# Power.net
KiCad netlist of a schematic drawn in Altium Designer
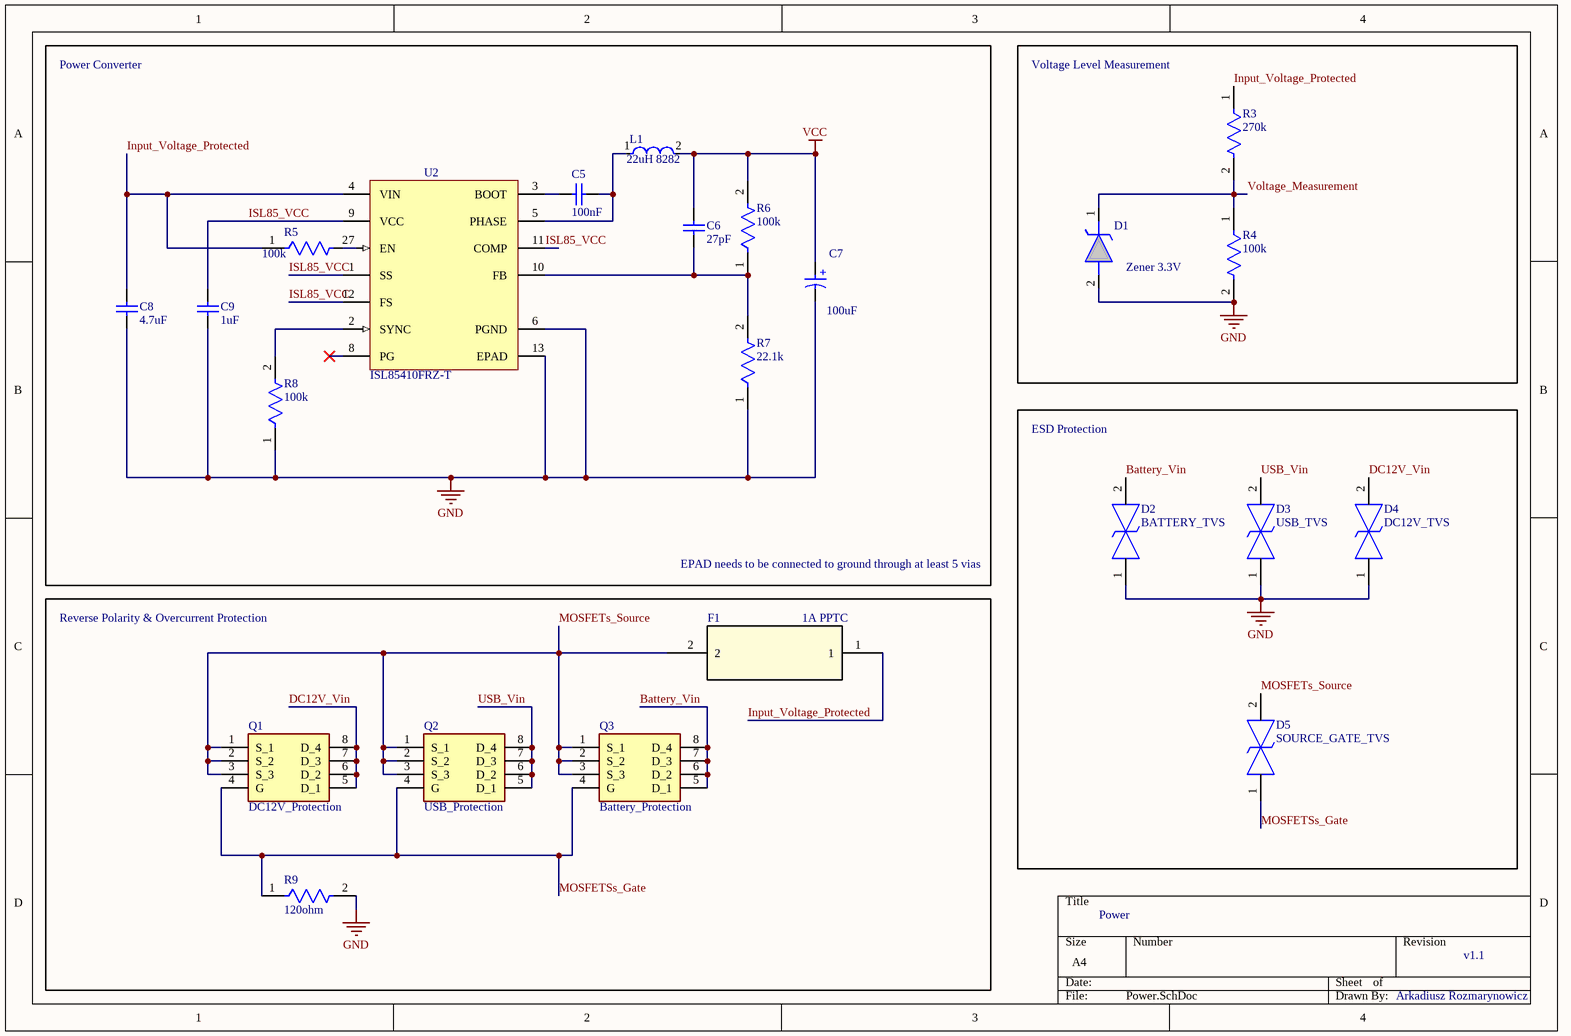
[diagram p0: Power.SchDoc]

(export (version "E")
  (design (tool "Eeschema 10.0.6"))
  (components
    (comp (ref "C5")
      (value "100nF")
      (footprint "CAPC2013X145X48NL20T23")
      (fields (field (name "PART NUMBER") "VJ0805Y104KXAMR") (field (name "MANUFACTURER") "Vitramon"))
      (libsource (lib "Altium Content Vault") (part "CAP"))
    )
    (comp (ref "C6")
      (value "27pF")
      (footprint "CAPC2013X145X48NL20T23")
      (fields (field (name "PART NUMBER") "VJ0805Y104KXAMR") (field (name "MANUFACTURER") "Vitramon"))
      (libsource (lib "Altium Content Vault") (part "CAP"))
    )
    (comp (ref "C7")
      (value "100uF")
      (footprint "WCAP-ASLI_D6.3H7.7")
      (description "Cap Aluminum Lytic 100uF 35V 20% (6.3 X 7.7mm) SMD 300mA 2000h 105C T/R")
      (fields (field (name "TOLERANCE") "20%"))
      (libsource (lib "Altium Content Vault") (part "Capacitor_Polarized"))
    )
    (comp (ref "C8")
      (value "4.7uF")
      (footprint "CAPC2013X145X48NL20T23")
      (fields (field (name "PART NUMBER") "VJ0805Y104KXAMR") (field (name "MANUFACTURER") "Vitramon"))
      (libsource (lib "Altium Content Vault") (part "CAP"))
    )
    (comp (ref "C9")
      (value "1uF")
      (footprint "CAPC2013X145X48NL20T23")
      (fields (field (name "PART NUMBER") "VJ0805Y104KXAMR") (field (name "MANUFACTURER") "Vitramon"))
      (libsource (lib "Altium Content Vault") (part "CAP"))
    )
    (comp (ref "D1")
      (value "Zener 3.3V")
      (footprint "ZMM33B")
      (description "SMD Planra Zener Diode")
      (fields
        (field (name "MANUFACTURER_PART_NUMBER") "ZMM33B")
        (field (name "MOUSER PART NUMBER") "637-ZMM33B")
      )
      (libsource (lib "ZMM33B") (part "ZMM33B"))
    )
    (comp (ref "D2")
      (value "BATTERY_TVS")
      (footprint "DIONM5127X250N")
      (description "19.9V Clamp 30.2A Ipp Tvs Diode Surface Mount DO-214AC (SMA)")
      (fields (field (name "MANUFACTURER_PART_NUMBER") "SMAJ12CA-HP6AT/13"))
      (libsource (lib "SMAJ12CA-HP6AT_13") (part "SMAJ12CA-HP6AT_13"))
    )
    (comp (ref "D3")
      (value "USB_TVS")
      (footprint "DIONM5127X250N")
      (description "19.9V Clamp 30.2A Ipp Tvs Diode Surface Mount DO-214AC (SMA)")
      (fields (field (name "MANUFACTURER_PART_NUMBER") "SMAJ12CA-HP6AT/13"))
      (libsource (lib "SMAJ12CA-HP6AT_13") (part "SMAJ12CA-HP6AT_13"))
    )
    (comp (ref "D4")
      (value "DC12V_TVS")
      (footprint "DIONM5127X250N")
      (description "19.9V Clamp 30.2A Ipp Tvs Diode Surface Mount DO-214AC (SMA)")
      (fields (field (name "MANUFACTURER_PART_NUMBER") "SMAJ12CA-HP6AT/13"))
      (libsource (lib "SMAJ12CA-HP6AT_13") (part "SMAJ12CA-HP6AT_13"))
    )
    (comp (ref "D5")
      (value "SOURCE_GATE_TVS")
      (footprint "DIONM5127X250N")
      (description "19.9V Clamp 30.2A Ipp Tvs Diode Surface Mount DO-214AC (SMA)")
      (fields (field (name "MANUFACTURER_PART_NUMBER") "SMAJ12CA-HP6AT/13"))
      (libsource (lib "SMAJ12CA-HP6AT_13") (part "SMAJ12CA-HP6AT_13"))
    )
    (comp (ref "F1")
      (value "1A PPTC")
      (footprint "CHIP_ 0603L_1P8X1_LTF")
      (description "PPTC")
      (fields
        (field (name "MANUFACTURER_PART_NUMBER") "0603L100SLYR")
        (field (name "COPYRIGHT") "Copyright (C) 2025 Ultra Librarian. All rights reserved.")
      )
      (libsource (lib "0603L100SLYR") (part "0603L100SLYR"))
    )
    (comp (ref "L1")
      (value "22uH 8282")
      (footprint "FP-IHLP-3232DZ-FP_2_413x5-MFG")
      (description "Commercial Inductors, High Temperature (155 °C) Series 22uH 3.7A 110.21mΩ 20%")
      (fields (field (name "TOLERANCE") "20%"))
      (libsource (lib "Altium Content Vault") (part "725321dda6339637d4d059423bc1c3c"))
    )
    (comp (ref "Q1")
      (value "DC12V_Protection")
      (footprint "SOIC127P600X170-8N")
      (description "MOSFET P Channel 30V 7.1A 2.1V @ 250uA 45m @ 6A,10V SOP-8_150mil RoHS")
      (fields
        (field (name "MANUFACTURER_PART_NUMBER") "DMP3056LSS-13")
        (field (name "MOUSER PART NUMBER") "621-DMP3056LSS-13")
      )
      (libsource (lib "DMP3056LSS-13") (part "DMP3056LSS-13"))
    )
    (comp (ref "Q2")
      (value "USB_Protection")
      (footprint "SOIC127P600X170-8N")
      (description "MOSFET P Channel 30V 7.1A 2.1V @ 250uA 45m @ 6A,10V SOP-8_150mil RoHS")
      (fields
        (field (name "MANUFACTURER_PART_NUMBER") "DMP3056LSS-13")
        (field (name "MOUSER PART NUMBER") "621-DMP3056LSS-13")
      )
      (libsource (lib "DMP3056LSS-13") (part "DMP3056LSS-13"))
    )
    (comp (ref "Q3")
      (value "Battery_Protection")
      (footprint "SOIC127P600X170-8N")
      (description "MOSFET P Channel 30V 7.1A 2.1V @ 250uA 45m @ 6A,10V SOP-8_150mil RoHS")
      (fields
        (field (name "MANUFACTURER_PART_NUMBER") "DMP3056LSS-13")
        (field (name "MOUSER PART NUMBER") "621-DMP3056LSS-13")
      )
      (libsource (lib "DMP3056LSS-13") (part "DMP3056LSS-13"))
    )
    (comp (ref "R3")
      (value "270k")
      (footprint "FP-CRGCQ0805-IPC_C")
      (description "CRGCQ0805 10KΩ 0.125W ±100ppm/°C 5% 150V")
      (fields
        (field (name "TOLERANCE") "0.05")
        (field (name "OCTOPART") "https://octopart.com/crgcq0805j100k-te+connectivity-91018199")
      )
      (libsource (lib "Altium Content Vault") (part "1029c3af85768c4190bb7ad29bc67b5"))
    )
    (comp (ref "R4")
      (value "100k")
      (footprint "FP-CRGCQ0805-IPC_C")
      (description "CRGCQ0805 10KΩ 0.125W ±100ppm/°C 5% 150V")
      (fields
        (field (name "TOLERANCE") "0.05")
        (field (name "OCTOPART") "https://octopart.com/crgcq0805j100k-te+connectivity-91018199")
      )
      (libsource (lib "Altium Content Vault") (part "1029c3af85768c4190bb7ad29bc67b5"))
    )
    (comp (ref "R5")
      (value "100k")
      (footprint "FP-CRGCQ0805-IPC_C")
      (description "CRGCQ0805 100KΩ 0.125W ±100ppm/°C 5% 150V")
      (fields
        (field (name "TOLERANCE") "0.05")
        (field (name "OCTOPART") "https://octopart.com/crgcq0805j100k-te+connectivity-91018199")
      )
      (libsource (lib "Altium Content Vault") (part "1029c3af85768c4190bb7ad29bc67b5"))
    )
    (comp (ref "R6")
      (value "100k")
      (footprint "FP-CRGCQ0805-IPC_C")
      (description "CRGCQ0805 100KΩ 0.125W ±100ppm/°C 5% 150V")
      (fields
        (field (name "TOLERANCE") "0.05")
        (field (name "OCTOPART") "https://octopart.com/crgcq0805j100k-te+connectivity-91018199")
      )
      (libsource (lib "Altium Content Vault") (part "1029c3af85768c4190bb7ad29bc67b5"))
    )
    (comp (ref "R7")
      (value "22.1k")
      (footprint "FP-CRGCQ0805-IPC_C")
      (description "CRGCQ0805 100KΩ 0.125W ±100ppm/°C 5% 150V")
      (fields
        (field (name "TOLERANCE") "0.05")
        (field (name "OCTOPART") "https://octopart.com/crgcq0805j100k-te+connectivity-91018199")
      )
      (libsource (lib "Altium Content Vault") (part "1029c3af85768c4190bb7ad29bc67b5"))
    )
    (comp (ref "R8")
      (value "100k")
      (footprint "FP-CRGCQ0805-IPC_C")
      (description "CRGCQ0805 100KΩ 0.125W ±100ppm/°C 5% 150V")
      (fields
        (field (name "TOLERANCE") "0.05")
        (field (name "OCTOPART") "https://octopart.com/crgcq0805j100k-te+connectivity-91018199")
      )
      (libsource (lib "Altium Content Vault") (part "1029c3af85768c4190bb7ad29bc67b5"))
    )
    (comp (ref "R9")
      (value "120ohm")
      (footprint "FP-CRGCQ0805-IPC_C")
      (description "CRGCQ0805 10KΩ 0.125W ±100ppm/°C 5% 150V")
      (fields
        (field (name "TOLERANCE") "0.05")
        (field (name "OCTOPART") "https://octopart.com/crgcq0805j100k-te+connectivity-91018199")
      )
      (libsource (lib "Altium Content Vault") (part "1029c3af85768c4190bb7ad29bc67b5"))
    )
    (comp (ref "U2")
      (value "ISL85410FRZ-T")
      (footprint "L12_4x3_MFG")
      (description "Inverter RoHS Compliant Adjustable Positive Switching Regulator IC 125C 2MHz 1A 82.298666mg")
      (libsource (lib "Altium Content Vault") (part "27339be89be241b5cf71551e81944d9"))
    )
  )
  (nets
    (net (code "1") (name "/Battery_Vin") (class "Default")
      (node (ref "D2") (pin "2") (pinfunction "2_2") (pintype "passive"))
      (node (ref "Q3") (pin "5") (pinfunction "D_1_5") (pintype "passive"))
      (node (ref "Q3") (pin "6") (pinfunction "D_2_6") (pintype "passive"))
      (node (ref "Q3") (pin "7") (pinfunction "D_3_7") (pintype "passive"))
      (node (ref "Q3") (pin "8") (pinfunction "D_4_8") (pintype "passive"))
    )
    (net (code "2") (name "/DC12V_Vin") (class "Default")
      (node (ref "D4") (pin "2") (pinfunction "2_2") (pintype "passive"))
      (node (ref "Q1") (pin "5") (pinfunction "D_1_5") (pintype "passive"))
      (node (ref "Q1") (pin "6") (pinfunction "D_2_6") (pintype "passive"))
      (node (ref "Q1") (pin "7") (pinfunction "D_3_7") (pintype "passive"))
      (node (ref "Q1") (pin "8") (pinfunction "D_4_8") (pintype "passive"))
    )
    (net (code "3") (name "/ISL85_VCC") (class "Default")
      (node (ref "C9") (pin "2") (pinfunction "2_2") (pintype "passive"))
      (node (ref "U2") (pin "1") (pinfunction "SS_1") (pintype "passive"))
      (node (ref "U2") (pin "11") (pinfunction "COMP_11") (pintype "passive"))
      (node (ref "U2") (pin "12") (pinfunction "FS_12") (pintype "passive"))
      (node (ref "U2") (pin "9") (pinfunction "VCC_9") (pintype "power_in"))
    )
    (net (code "4") (name "/Input_Voltage_Protected") (class "Default")
      (node (ref "C8") (pin "2") (pinfunction "2_2") (pintype "passive"))
      (node (ref "F1") (pin "1") (pinfunction "1_1") (pintype "passive"))
      (node (ref "R3") (pin "1") (pinfunction "1_1") (pintype "passive"))
      (node (ref "R5") (pin "1") (pinfunction "1_1") (pintype "passive"))
      (node (ref "U2") (pin "4") (pinfunction "VIN_4") (pintype "power_in"))
    )
    (net (code "5") (name "/MOSFETSs_Gate") (class "Default")
      (node (ref "D5") (pin "1") (pinfunction "1_1") (pintype "passive"))
      (node (ref "Q1") (pin "4") (pinfunction "G_4") (pintype "passive"))
      (node (ref "Q2") (pin "4") (pinfunction "G_4") (pintype "passive"))
      (node (ref "Q3") (pin "4") (pinfunction "G_4") (pintype "passive"))
      (node (ref "R9") (pin "1") (pinfunction "1_1") (pintype "passive"))
    )
    (net (code "6") (name "/MOSFETs_Source") (class "Default")
      (node (ref "D5") (pin "2") (pinfunction "2_2") (pintype "passive"))
      (node (ref "F1") (pin "2") (pinfunction "2_2") (pintype "passive"))
      (node (ref "Q1") (pin "1") (pinfunction "S_1_1") (pintype "passive"))
      (node (ref "Q1") (pin "2") (pinfunction "S_2_2") (pintype "passive"))
      (node (ref "Q1") (pin "3") (pinfunction "S_3_3") (pintype "passive"))
      (node (ref "Q2") (pin "1") (pinfunction "S_1_1") (pintype "passive"))
      (node (ref "Q2") (pin "2") (pinfunction "S_2_2") (pintype "passive"))
      (node (ref "Q2") (pin "3") (pinfunction "S_3_3") (pintype "passive"))
      (node (ref "Q3") (pin "1") (pinfunction "S_1_1") (pintype "passive"))
      (node (ref "Q3") (pin "2") (pinfunction "S_2_2") (pintype "passive"))
      (node (ref "Q3") (pin "3") (pinfunction "S_3_3") (pintype "passive"))
    )
    (net (code "7") (name "/USB_Vin") (class "Default")
      (node (ref "D3") (pin "2") (pinfunction "2_2") (pintype "passive"))
      (node (ref "Q2") (pin "5") (pinfunction "D_1_5") (pintype "passive"))
      (node (ref "Q2") (pin "6") (pinfunction "D_2_6") (pintype "passive"))
      (node (ref "Q2") (pin "7") (pinfunction "D_3_7") (pintype "passive"))
      (node (ref "Q2") (pin "8") (pinfunction "D_4_8") (pintype "passive"))
    )
    (net (code "8") (name "/Voltage_Measurement") (class "Default")
      (node (ref "D1") (pin "1") (pinfunction "K_1") (pintype "passive"))
      (node (ref "R3") (pin "2") (pinfunction "2_2") (pintype "passive"))
      (node (ref "R4") (pin "1") (pinfunction "1_1") (pintype "passive"))
    )
    (net (code "9") (name "GND") (class "Default")
      (node (ref "C7") (pin "2") (pinfunction "N_2") (pintype "passive"))
      (node (ref "C8") (pin "1") (pinfunction "1_1") (pintype "passive"))
      (node (ref "C9") (pin "1") (pinfunction "1_1") (pintype "passive"))
      (node (ref "D1") (pin "2") (pinfunction "A_2") (pintype "passive"))
      (node (ref "D2") (pin "1") (pinfunction "1_1") (pintype "passive"))
      (node (ref "D3") (pin "1") (pinfunction "1_1") (pintype "passive"))
      (node (ref "D4") (pin "1") (pinfunction "1_1") (pintype "passive"))
      (node (ref "R4") (pin "2") (pinfunction "2_2") (pintype "passive"))
      (node (ref "R7") (pin "1") (pinfunction "1_1") (pintype "passive"))
      (node (ref "R8") (pin "1") (pinfunction "1_1") (pintype "passive"))
      (node (ref "R9") (pin "2") (pinfunction "2_2") (pintype "passive"))
      (node (ref "U2") (pin "13") (pinfunction "EPAD_13") (pintype "power_in"))
      (node (ref "U2") (pin "6") (pinfunction "PGND_6") (pintype "power_in"))
    )
    (net (code "10") (name "Net-(U2-BOOT)") (class "Default")
      (node (ref "C5") (pin "2") (pinfunction "2_2") (pintype "passive"))
      (node (ref "U2") (pin "3") (pinfunction "BOOT_3") (pintype "passive"))
    )
    (net (code "11") (name "Net-(U2-EN)") (class "Default")
      (node (ref "R5") (pin "2") (pinfunction "2_2") (pintype "passive"))
      (node (ref "U2") (pin "7") (pinfunction "EN_7") (pintype "input"))
    )
    (net (code "12") (name "Net-(U2-FB)") (class "Default")
      (node (ref "C6") (pin "1") (pinfunction "1_1") (pintype "passive"))
      (node (ref "R6") (pin "1") (pinfunction "1_1") (pintype "passive"))
      (node (ref "R7") (pin "2") (pinfunction "2_2") (pintype "passive"))
      (node (ref "U2") (pin "10") (pinfunction "FB_10") (pintype "passive"))
    )
    (net (code "13") (name "Net-(U2-PHASE)") (class "Default")
      (node (ref "C5") (pin "1") (pinfunction "1_1") (pintype "passive"))
      (node (ref "L1") (pin "1") (pinfunction "1_1") (pintype "passive"))
      (node (ref "U2") (pin "5") (pinfunction "PHASE_5") (pintype "passive"))
    )
    (net (code "14") (name "Net-(U2-SYNC)") (class "Default")
      (node (ref "R8") (pin "2") (pinfunction "2_2") (pintype "passive"))
      (node (ref "U2") (pin "2") (pinfunction "SYNC_2") (pintype "input"))
    )
    (net (code "15") (name "VCC") (class "Default")
      (node (ref "C6") (pin "2") (pinfunction "2_2") (pintype "passive"))
      (node (ref "C7") (pin "1") (pinfunction "P_1") (pintype "passive"))
      (node (ref "L1") (pin "2") (pinfunction "2_2") (pintype "passive"))
      (node (ref "R6") (pin "2") (pinfunction "2_2") (pintype "passive"))
    )
    (net (code "16") (name "unconnected-(U2-PG-Pad8)") (class "Default")
      (node (ref "U2") (pin "8") (pinfunction "PG_8") (pintype "open_collector+no_connect"))
    )
  )
)
